# Power.net
KiCad netlist of a schematic drawn in Altium Designer
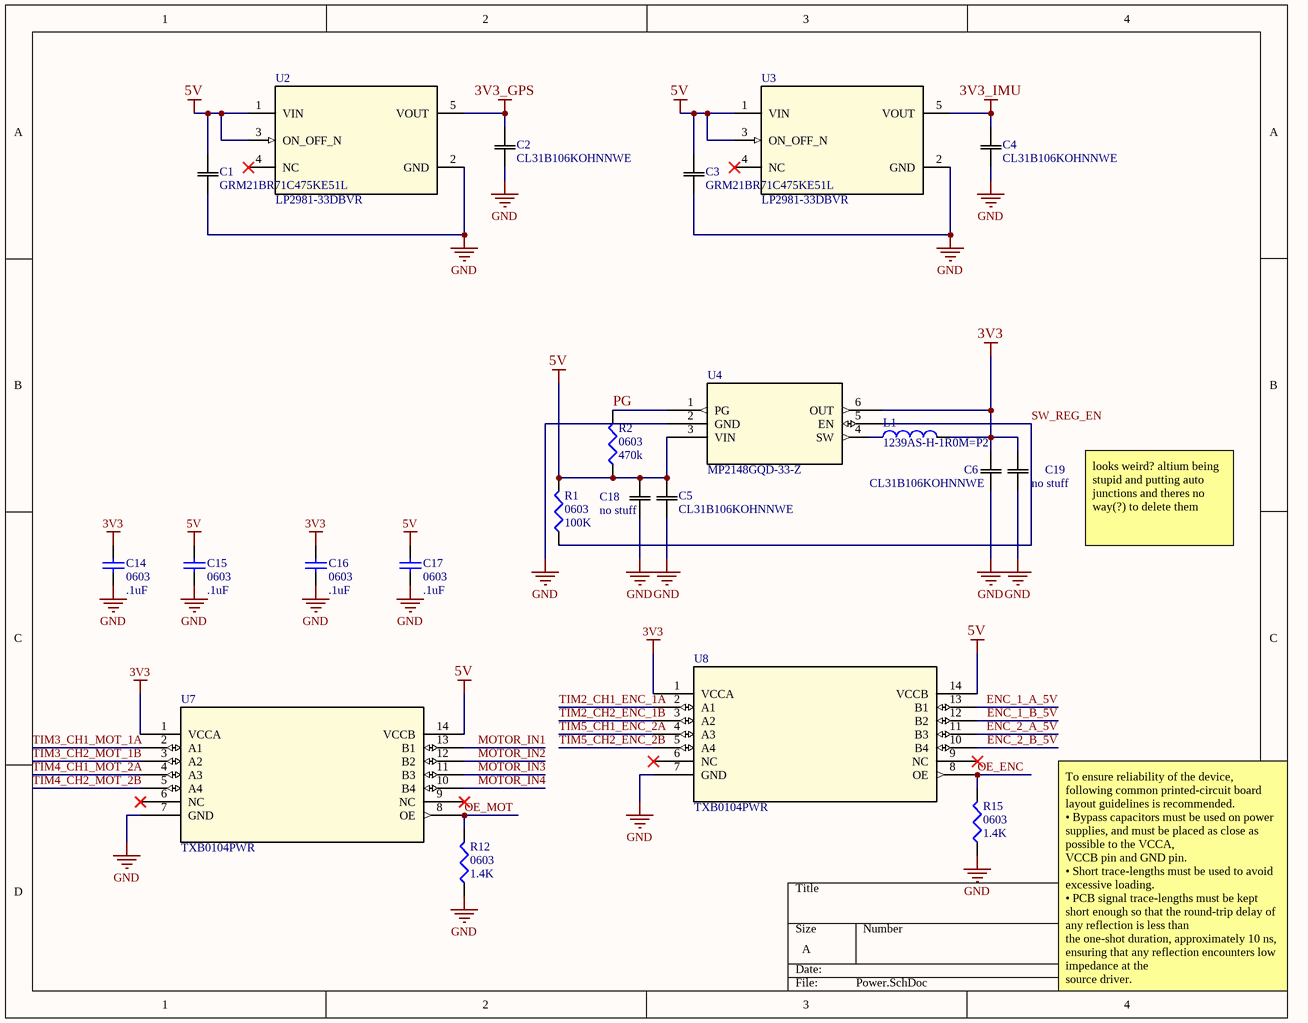
[diagram p0: Power.SchDoc]

(export (version "E")
  (design (tool "Eeschema 10.0.6"))
  (components
    (comp (ref "C1")
      (value "GRM21BR71C475KE51L")
      (footprint "swarm_crawler_pcb:CAP_GRM0805_2X1P25_MUR")
      (description "No Description Available")
      (fields (field (name "COPYRIGHT") "Copyright (C) 2023 Ultra Librarian. All rights reserved."))
      (libsource (lib "swarm_crawler_sch") (part "GRM21BR71C475KE51L"))
    )
    (comp (ref "C2")
      (value "CL31B106KOHNNWE")
      (footprint "swarm_crawler_pcb:CAP_CL31_SAM")
      (description "No Description Available")
      (fields (field (name "COPYRIGHT") "Copyright (C) 2023 Ultra Librarian. All rights reserved."))
      (libsource (lib "swarm_crawler_sch") (part "CL31B106KOHNNWE"))
    )
    (comp (ref "C3")
      (value "GRM21BR71C475KE51L")
      (footprint "swarm_crawler_pcb:CAP_GRM0805_2X1P25_MUR")
      (description "No Description Available")
      (fields (field (name "COPYRIGHT") "Copyright (C) 2023 Ultra Librarian. All rights reserved."))
      (libsource (lib "swarm_crawler_sch") (part "GRM21BR71C475KE51L"))
    )
    (comp (ref "C4")
      (value "CL31B106KOHNNWE")
      (footprint "swarm_crawler_pcb:CAP_CL31_SAM")
      (description "No Description Available")
      (fields (field (name "COPYRIGHT") "Copyright (C) 2023 Ultra Librarian. All rights reserved."))
      (libsource (lib "swarm_crawler_sch") (part "CL31B106KOHNNWE"))
    )
    (comp (ref "C5")
      (value "CL31B106KOHNNWE")
      (footprint "swarm_crawler_pcb:CAP_CL31_SAM")
      (description "No Description Available")
      (fields (field (name "COPYRIGHT") "Copyright (C) 2023 Ultra Librarian. All rights reserved."))
      (libsource (lib "swarm_crawler_sch") (part "CL31B106KOHNNWE"))
    )
    (comp (ref "C6")
      (value "CL31B106KOHNNWE")
      (footprint "swarm_crawler_pcb:CAP_CL31_SAM")
      (description "No Description Available")
      (fields (field (name "COPYRIGHT") "Copyright (C) 2023 Ultra Librarian. All rights reserved."))
      (libsource (lib "swarm_crawler_sch") (part "CL31B106KOHNNWE"))
    )
    (comp (ref "C14")
      (value "0603")
      (footprint "1608[0603]")
      (description "Capacitor (Semiconductor SIM Model)")
      (fields (field (name "ALTIUM_VALUE") ".1uF") (field (name "PUBLISHER") "Altium Limited"))
      (libsource (lib "Miscellaneous Devices") (part "Cap Semi"))
    )
    (comp (ref "C15")
      (value "0603")
      (footprint "1608[0603]")
      (description "Capacitor (Semiconductor SIM Model)")
      (fields (field (name "ALTIUM_VALUE") ".1uF") (field (name "PUBLISHER") "Altium Limited"))
      (libsource (lib "Miscellaneous Devices") (part "Cap Semi"))
    )
    (comp (ref "C16")
      (value "0603")
      (footprint "1608[0603]")
      (description "Capacitor (Semiconductor SIM Model)")
      (fields (field (name "ALTIUM_VALUE") ".1uF") (field (name "PUBLISHER") "Altium Limited"))
      (libsource (lib "Miscellaneous Devices") (part "Cap Semi"))
    )
    (comp (ref "C17")
      (value "0603")
      (footprint "1608[0603]")
      (description "Capacitor (Semiconductor SIM Model)")
      (fields (field (name "ALTIUM_VALUE") ".1uF") (field (name "PUBLISHER") "Altium Limited"))
      (libsource (lib "Miscellaneous Devices") (part "Cap Semi"))
    )
    (comp (ref "C18")
      (value "no stuff")
      (footprint "swarm_crawler_pcb:CAP_CL31_SAM")
      (description "No Description Available")
      (fields
        (field (name "MANUFACTURER_PART_NUMBER") "CL31B106KOHNNWE")
        (field (name "COPYRIGHT") "Copyright (C) 2023 Ultra Librarian. All rights reserved.")
      )
      (libsource (lib "swarm_crawler_sch") (part "CL31B106KOHNNWE"))
    )
    (comp (ref "C19")
      (value "no stuff")
      (footprint "swarm_crawler_pcb:CAP_CL31_SAM")
      (description "No Description Available")
      (fields
        (field (name "MANUFACTURER_PART_NUMBER") "CL31B106KOHNNWE")
        (field (name "COPYRIGHT") "Copyright (C) 2023 Ultra Librarian. All rights reserved.")
      )
      (libsource (lib "swarm_crawler_sch") (part "CL31B106KOHNNWE"))
    )
    (comp (ref "L1")
      (value "1239AS-H-1R0M=P2")
      (footprint "swarm_crawler_pcb:CAPC10555_55N_KEM")
      (description "Inductor with Inductance: 1uH Tol. +/-20%, Package: 1008 _2520_")
      (fields (field (name "DIGI-KEY_PART_NUMBER") "490-10564-1-ND") (field (name "MF") "Murata Electronics"))
      (libsource (lib "swarm_crawler_sch") (part "1239AS-H-1R0M=P2"))
    )
    (comp (ref "R1")
      (value "0603")
      (footprint "J1-0603")
      (description "Resistor")
      (fields (field (name "ALTIUM_VALUE") "100K") (field (name "PUBLISHER") "Altium Limited"))
      (libsource (lib "Miscellaneous Devices") (part "Res3"))
    )
    (comp (ref "R2")
      (value "0603")
      (footprint "J1-0603")
      (description "Resistor")
      (fields (field (name "ALTIUM_VALUE") "470k") (field (name "PUBLISHER") "Altium Limited"))
      (libsource (lib "Miscellaneous Devices") (part "Res3"))
    )
    (comp (ref "R12")
      (value "0603")
      (footprint "J1-0603")
      (description "Resistor")
      (fields (field (name "ALTIUM_VALUE") "1.4K") (field (name "PUBLISHER") "Altium Limited"))
      (libsource (lib "Miscellaneous Devices") (part "Res3"))
    )
    (comp (ref "R15")
      (value "0603")
      (footprint "J1-0603")
      (description "Resistor")
      (fields (field (name "ALTIUM_VALUE") "1.4K") (field (name "PUBLISHER") "Altium Limited"))
      (libsource (lib "Miscellaneous Devices") (part "Res3"))
    )
    (comp (ref "U2")
      (value "LP2981-33DBVR")
      (footprint "swarm_crawler_pcb:DBV0005A_N")
      (description "No Description Available")
      (fields (field (name "COPYRIGHT") "Copyright (C) 2023 Ultra Librarian. All rights reserved."))
      (libsource (lib "swarm_crawler_sch") (part "LP2981-33DBVR"))
    )
    (comp (ref "U3")
      (value "LP2981-33DBVR")
      (footprint "swarm_crawler_pcb:DBV0005A_N")
      (description "No Description Available")
      (fields (field (name "COPYRIGHT") "Copyright (C) 2023 Ultra Librarian. All rights reserved."))
      (libsource (lib "swarm_crawler_sch") (part "LP2981-33DBVR"))
    )
    (comp (ref "U4")
      (value "MP2148GQD-33-Z")
      (footprint "swarm_crawler_pcb:QFN-1p0x1p5_MNP")
      (description "No Description Available")
      (fields (field (name "COPYRIGHT") "Copyright (C) 2023 Ultra Librarian. All rights reserved."))
      (libsource (lib "swarm_crawler_sch") (part "MP2148GQD-33-Z"))
    )
    (comp (ref "U7")
      (value "TXB0104PWR")
      (footprint "swarm_crawler_pcb:PW14")
      (description "No Description Available")
      (fields (field (name "COPYRIGHT") "Copyright (C) 2023 Ultra Librarian. All rights reserved."))
      (libsource (lib "swarm_crawler_sch") (part "TXB0104PWR"))
    )
    (comp (ref "U8")
      (value "TXB0104PWR")
      (footprint "swarm_crawler_pcb:PW14")
      (description "No Description Available")
      (fields (field (name "COPYRIGHT") "Copyright (C) 2023 Ultra Librarian. All rights reserved."))
      (libsource (lib "swarm_crawler_sch") (part "TXB0104PWR"))
    )
  )
  (nets
    (net (code "1") (name "/ENC_1_A_5V") (class "Default")
      (node (ref "U8") (pin "13") (pinfunction "B1_13") (pintype "bidirectional"))
    )
    (net (code "2") (name "/ENC_1_B_5V") (class "Default")
      (node (ref "U8") (pin "12") (pinfunction "B2_12") (pintype "bidirectional"))
    )
    (net (code "3") (name "/ENC_2_A_5V") (class "Default")
      (node (ref "U8") (pin "11") (pinfunction "B3_11") (pintype "bidirectional"))
    )
    (net (code "4") (name "/ENC_2_B_5V") (class "Default")
      (node (ref "U8") (pin "10") (pinfunction "B4_10") (pintype "bidirectional"))
    )
    (net (code "5") (name "/MOTOR_IN1") (class "Default")
      (node (ref "U7") (pin "13") (pinfunction "B1_13") (pintype "bidirectional"))
    )
    (net (code "6") (name "/MOTOR_IN2") (class "Default")
      (node (ref "U7") (pin "12") (pinfunction "B2_12") (pintype "bidirectional"))
    )
    (net (code "7") (name "/MOTOR_IN3") (class "Default")
      (node (ref "U7") (pin "11") (pinfunction "B3_11") (pintype "bidirectional"))
    )
    (net (code "8") (name "/MOTOR_IN4") (class "Default")
      (node (ref "U7") (pin "10") (pinfunction "B4_10") (pintype "bidirectional"))
    )
    (net (code "9") (name "/OE_ENC") (class "Default")
      (node (ref "R15") (pin "2") (pinfunction "2_2") (pintype "passive"))
      (node (ref "U8") (pin "8") (pinfunction "OE_8") (pintype "output"))
    )
    (net (code "10") (name "/OE_MOT") (class "Default")
      (node (ref "R12") (pin "2") (pinfunction "2_2") (pintype "passive"))
      (node (ref "U7") (pin "8") (pinfunction "OE_8") (pintype "output"))
    )
    (net (code "11") (name "/PG") (class "Default")
      (node (ref "R2") (pin "2") (pinfunction "2_2") (pintype "passive"))
      (node (ref "U4") (pin "1") (pinfunction "PG_1") (pintype "output"))
    )
    (net (code "12") (name "/SW_REG_EN") (class "Default")
      (node (ref "R1") (pin "1") (pinfunction "1_1") (pintype "passive"))
      (node (ref "U4") (pin "5") (pinfunction "EN_5") (pintype "bidirectional"))
    )
    (net (code "13") (name "/TIM2_CH1_ENC_1A") (class "Default")
      (node (ref "U8") (pin "2") (pinfunction "A1_2") (pintype "bidirectional"))
    )
    (net (code "14") (name "/TIM2_CH2_ENC_1B") (class "Default")
      (node (ref "U8") (pin "3") (pinfunction "A2_3") (pintype "bidirectional"))
    )
    (net (code "15") (name "/TIM3_CH1_MOT_1A") (class "Default")
      (node (ref "U7") (pin "2") (pinfunction "A1_2") (pintype "bidirectional"))
    )
    (net (code "16") (name "/TIM3_CH2_MOT_1B") (class "Default")
      (node (ref "U7") (pin "3") (pinfunction "A2_3") (pintype "bidirectional"))
    )
    (net (code "17") (name "/TIM4_CH1_MOT_2A") (class "Default")
      (node (ref "U7") (pin "4") (pinfunction "A3_4") (pintype "bidirectional"))
    )
    (net (code "18") (name "/TIM4_CH2_MOT_2B") (class "Default")
      (node (ref "U7") (pin "5") (pinfunction "A4_5") (pintype "bidirectional"))
    )
    (net (code "19") (name "/TIM5_CH1_ENC_2A") (class "Default")
      (node (ref "U8") (pin "4") (pinfunction "A3_4") (pintype "bidirectional"))
    )
    (net (code "20") (name "/TIM5_CH2_ENC_2B") (class "Default")
      (node (ref "U8") (pin "5") (pinfunction "A4_5") (pintype "bidirectional"))
    )
    (net (code "21") (name "3V3") (class "Default")
      (node (ref "C14") (pin "2") (pinfunction "2_2") (pintype "passive"))
      (node (ref "C16") (pin "2") (pinfunction "2_2") (pintype "passive"))
      (node (ref "C19") (pin "2") (pinfunction "2_2") (pintype "passive"))
      (node (ref "C6") (pin "2") (pinfunction "2_2") (pintype "passive"))
      (node (ref "L1") (pin "2") (pinfunction "2_2") (pintype "passive"))
      (node (ref "U4") (pin "6") (pinfunction "OUT_6") (pintype "output"))
      (node (ref "U7") (pin "1") (pinfunction "VCCA_1") (pintype "power_in"))
      (node (ref "U8") (pin "1") (pinfunction "VCCA_1") (pintype "power_in"))
    )
    (net (code "22") (name "3V3_GPS") (class "Default")
      (node (ref "C2") (pin "2") (pinfunction "2_2") (pintype "passive"))
      (node (ref "U2") (pin "5") (pinfunction "VOUT_5") (pintype "power_in"))
    )
    (net (code "23") (name "3V3_IMU") (class "Default")
      (node (ref "C4") (pin "2") (pinfunction "2_2") (pintype "passive"))
      (node (ref "U3") (pin "5") (pinfunction "VOUT_5") (pintype "power_in"))
    )
    (net (code "24") (name "5V") (class "Default")
      (node (ref "C1") (pin "2") (pinfunction "2_2") (pintype "passive"))
      (node (ref "C15") (pin "2") (pinfunction "2_2") (pintype "passive"))
      (node (ref "C17") (pin "2") (pinfunction "2_2") (pintype "passive"))
      (node (ref "C18") (pin "2") (pinfunction "2_2") (pintype "passive"))
      (node (ref "C3") (pin "2") (pinfunction "2_2") (pintype "passive"))
      (node (ref "C5") (pin "2") (pinfunction "2_2") (pintype "passive"))
      (node (ref "R1") (pin "2") (pinfunction "2_2") (pintype "passive"))
      (node (ref "R2") (pin "1") (pinfunction "1_1") (pintype "passive"))
      (node (ref "U2") (pin "1") (pinfunction "VIN_1") (pintype "power_in"))
      (node (ref "U2") (pin "3") (pinfunction "ON_OFF_N_3") (pintype "input"))
      (node (ref "U3") (pin "1") (pinfunction "VIN_1") (pintype "power_in"))
      (node (ref "U3") (pin "3") (pinfunction "ON_OFF_N_3") (pintype "input"))
      (node (ref "U4") (pin "3") (pinfunction "VIN_3") (pintype "power_in"))
      (node (ref "U7") (pin "14") (pinfunction "VCCB_14") (pintype "power_in"))
      (node (ref "U8") (pin "14") (pinfunction "VCCB_14") (pintype "power_in"))
    )
    (net (code "25") (name "GND") (class "Default")
      (node (ref "C1") (pin "1") (pinfunction "1_1") (pintype "passive"))
      (node (ref "C14") (pin "1") (pinfunction "1_1") (pintype "passive"))
      (node (ref "C15") (pin "1") (pinfunction "1_1") (pintype "passive"))
      (node (ref "C16") (pin "1") (pinfunction "1_1") (pintype "passive"))
      (node (ref "C17") (pin "1") (pinfunction "1_1") (pintype "passive"))
      (node (ref "C18") (pin "1") (pinfunction "1_1") (pintype "passive"))
      (node (ref "C19") (pin "1") (pinfunction "1_1") (pintype "passive"))
      (node (ref "C2") (pin "1") (pinfunction "1_1") (pintype "passive"))
      (node (ref "C3") (pin "1") (pinfunction "1_1") (pintype "passive"))
      (node (ref "C4") (pin "1") (pinfunction "1_1") (pintype "passive"))
      (node (ref "C5") (pin "1") (pinfunction "1_1") (pintype "passive"))
      (node (ref "C6") (pin "1") (pinfunction "1_1") (pintype "passive"))
      (node (ref "R12") (pin "1") (pinfunction "1_1") (pintype "passive"))
      (node (ref "R15") (pin "1") (pinfunction "1_1") (pintype "passive"))
      (node (ref "U2") (pin "2") (pinfunction "GND_2") (pintype "power_in"))
      (node (ref "U3") (pin "2") (pinfunction "GND_2") (pintype "power_in"))
      (node (ref "U4") (pin "2") (pinfunction "GND_2") (pintype "passive"))
      (node (ref "U7") (pin "7") (pinfunction "GND_7") (pintype "power_in"))
      (node (ref "U8") (pin "7") (pinfunction "GND_7") (pintype "power_in"))
    )
    (net (code "26") (name "Net-(U4-SW)") (class "Default")
      (node (ref "L1") (pin "1") (pinfunction "1_1") (pintype "passive"))
      (node (ref "U4") (pin "4") (pinfunction "SW_4") (pintype "output"))
    )
    (net (code "27") (name "unconnected-(U2-NC-Pad4)") (class "Default")
      (node (ref "U2") (pin "4") (pinfunction "NC_4") (pintype "passive+no_connect"))
    )
    (net (code "28") (name "unconnected-(U3-NC-Pad4)") (class "Default")
      (node (ref "U3") (pin "4") (pinfunction "NC_4") (pintype "passive+no_connect"))
    )
    (net (code "29") (name "unconnected-(U7-NC-Pad6)") (class "Default")
      (node (ref "U7") (pin "6") (pinfunction "NC_6") (pintype "passive+no_connect"))
    )
    (net (code "30") (name "unconnected-(U7-NC-Pad9)") (class "Default")
      (node (ref "U7") (pin "9") (pinfunction "NC_9") (pintype "passive+no_connect"))
    )
    (net (code "31") (name "unconnected-(U8-NC-Pad6)") (class "Default")
      (node (ref "U8") (pin "6") (pinfunction "NC_6") (pintype "passive+no_connect"))
    )
    (net (code "32") (name "unconnected-(U8-NC-Pad9)") (class "Default")
      (node (ref "U8") (pin "9") (pinfunction "NC_9") (pintype "passive+no_connect"))
    )
  )
)
